# Fused_Connections.net
KiCad netlist of a schematic drawn in Altium Designer
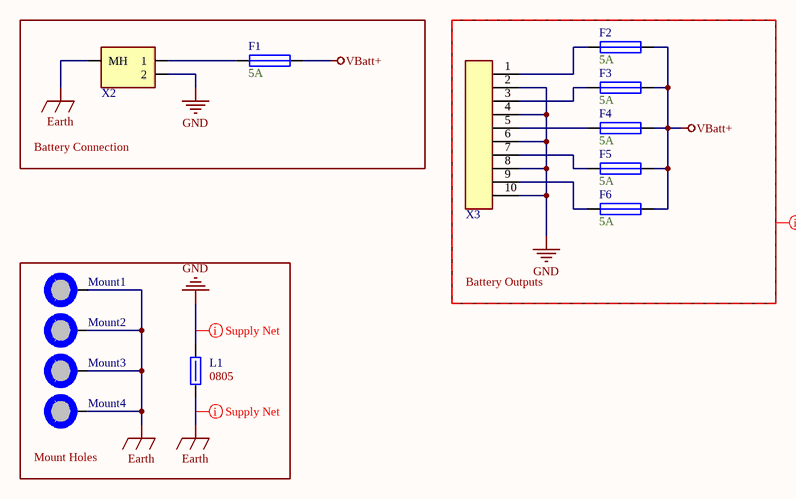
[diagram p0: Fused Connections.SchDoc]

(export (version "E")
  (design (tool "Eeschema 10.0.6"))
  (components
    (comp (ref "F1")
      (value "Mini")
      (footprint "[Mount] (Mini) Automotive Mount")
      (description "3568")
      (fields (field (name "AMPACITY") "5A"))
      (libsource (lib "Fuses") (part "[Mount] (Mini) Automotive Mount"))
    )
    (comp (ref "F2")
      (value "Mini")
      (footprint "[Mount] (Mini) Automotive Mount")
      (description "3568")
      (fields (field (name "AMPACITY") "5A"))
      (libsource (lib "Fuses") (part "[Mount] (Mini) Automotive Mount"))
    )
    (comp (ref "F3")
      (value "Mini")
      (footprint "[Mount] (Mini) Automotive Mount")
      (description "3568")
      (fields (field (name "AMPACITY") "5A"))
      (libsource (lib "Fuses") (part "[Mount] (Mini) Automotive Mount"))
    )
    (comp (ref "F4")
      (value "Mini")
      (footprint "[Mount] (Mini) Automotive Mount")
      (description "3568")
      (fields (field (name "AMPACITY") "5A"))
      (libsource (lib "Fuses") (part "[Mount] (Mini) Automotive Mount"))
    )
    (comp (ref "F5")
      (value "Mini")
      (footprint "[Mount] (Mini) Automotive Mount")
      (description "3568")
      (fields (field (name "AMPACITY") "5A"))
      (libsource (lib "Fuses") (part "[Mount] (Mini) Automotive Mount"))
    )
    (comp (ref "F6")
      (value "Mini")
      (footprint "[Mount] (Mini) Automotive Mount")
      (description "3568")
      (fields (field (name "AMPACITY") "5A"))
      (libsource (lib "Fuses") (part "[Mount] (Mini) Automotive Mount"))
    )
    (comp (ref "L1")
      (value "652-MH2029-300Y")
      (footprint "[Ferrite] SMD 0805")
      (fields (field (name "SIZE PACKAGE") "0805"))
      (libsource (lib "Ferrite Beads") (part "[Ferrite] SMD 0805 3A 30ohm"))
    )
    (comp (ref "Mount1")
      (value "M3 Mount Hole")
      (footprint "[Mount] M3 Mount Hole")
      (description "Place at least 4.5mm from board edge. Plated.")
      (libsource (lib "RADM Connectors") (part "[Mount] M3 Mount Hole"))
    )
    (comp (ref "Mount2")
      (value "M3 Mount Hole")
      (footprint "[Mount] M3 Mount Hole")
      (description "Place at least 4.5mm from board edge. Plated.")
      (libsource (lib "RADM Connectors") (part "[Mount] M3 Mount Hole"))
    )
    (comp (ref "Mount3")
      (value "M3 Mount Hole")
      (footprint "[Mount] M3 Mount Hole")
      (description "Place at least 4.5mm from board edge. Plated.")
      (libsource (lib "RADM Connectors") (part "[Mount] M3 Mount Hole"))
    )
    (comp (ref "Mount4")
      (value "M3 Mount Hole")
      (footprint "[Mount] M3 Mount Hole")
      (description "Place at least 4.5mm from board edge. Plated.")
      (libsource (lib "RADM Connectors") (part "[Mount] M3 Mount Hole"))
    )
    (comp (ref "X2")
      (value "Anderson 2pos Right-Angle")
      (footprint "[Anderson] 2pos Right-Angle 1327G17")
      (libsource (lib "Connectors") (part "[Anderson] 2pos Right-Angle"))
    )
    (comp (ref "X3")
      (value "10pin Screw Terminal")
      (footprint "[Screw Terminal] 10pin 5mm")
      (description "x5")
      (libsource (lib "Connectors") (part "[Screw Terminal] 10pin"))
    )
  )
  (nets
    (net (code "1") (name "Earth") (class "Default")
      (node (ref "L1") (pin "1") (pinfunction "1_1") (pintype "passive"))
      (node (ref "Mount1") (pin "1") (pintype "power_in"))
      (node (ref "Mount2") (pin "1") (pintype "power_in"))
      (node (ref "Mount3") (pin "1") (pintype "power_in"))
      (node (ref "Mount4") (pin "1") (pintype "power_in"))
      (node (ref "X2") (pin "MH") (pinfunction "MH_MH") (pintype "power_in"))
    )
    (net (code "2") (name "GND") (class "Default")
      (node (ref "L1") (pin "2") (pinfunction "2_2") (pintype "passive"))
      (node (ref "X2") (pin "2") (pinfunction "2_2") (pintype "passive"))
      (node (ref "X3") (pin "10") (pintype "power_in"))
      (node (ref "X3") (pin "2") (pintype "power_in"))
      (node (ref "X3") (pin "4") (pintype "power_in"))
      (node (ref "X3") (pin "6") (pintype "power_in"))
      (node (ref "X3") (pin "8") (pintype "power_in"))
    )
    (net (code "3") (name "Net-(F1-Pad1)") (class "Default")
      (node (ref "F1") (pin "1") (pinfunction "1_1") (pintype "passive"))
      (node (ref "X2") (pin "1") (pinfunction "1_1") (pintype "passive"))
    )
    (net (code "4") (name "Net-(F2-Pad1)") (class "Default")
      (node (ref "F2") (pin "1") (pinfunction "1_1") (pintype "passive"))
      (node (ref "X3") (pin "1") (pintype "power_in"))
    )
    (net (code "5") (name "Net-(F3-Pad1)") (class "Default")
      (node (ref "F3") (pin "1") (pinfunction "1_1") (pintype "passive"))
      (node (ref "X3") (pin "3") (pintype "power_in"))
    )
    (net (code "6") (name "Net-(F4-Pad1)") (class "Default")
      (node (ref "F4") (pin "1") (pinfunction "1_1") (pintype "passive"))
      (node (ref "X3") (pin "5") (pintype "power_in"))
    )
    (net (code "7") (name "Net-(F5-Pad1)") (class "Default")
      (node (ref "F5") (pin "1") (pinfunction "1_1") (pintype "passive"))
      (node (ref "X3") (pin "7") (pintype "power_in"))
    )
    (net (code "8") (name "Net-(F6-Pad1)") (class "Default")
      (node (ref "F6") (pin "1") (pinfunction "1_1") (pintype "passive"))
      (node (ref "X3") (pin "9") (pintype "power_in"))
    )
    (net (code "9") (name "VBatt+") (class "Default")
      (node (ref "F1") (pin "2") (pinfunction "2_2") (pintype "passive"))
      (node (ref "F2") (pin "2") (pinfunction "2_2") (pintype "passive"))
      (node (ref "F3") (pin "2") (pinfunction "2_2") (pintype "passive"))
      (node (ref "F4") (pin "2") (pinfunction "2_2") (pintype "passive"))
      (node (ref "F5") (pin "2") (pinfunction "2_2") (pintype "passive"))
      (node (ref "F6") (pin "2") (pinfunction "2_2") (pintype "passive"))
    )
  )
)
